# sensor.net
KiCad netlist of a schematic drawn in EAGLE
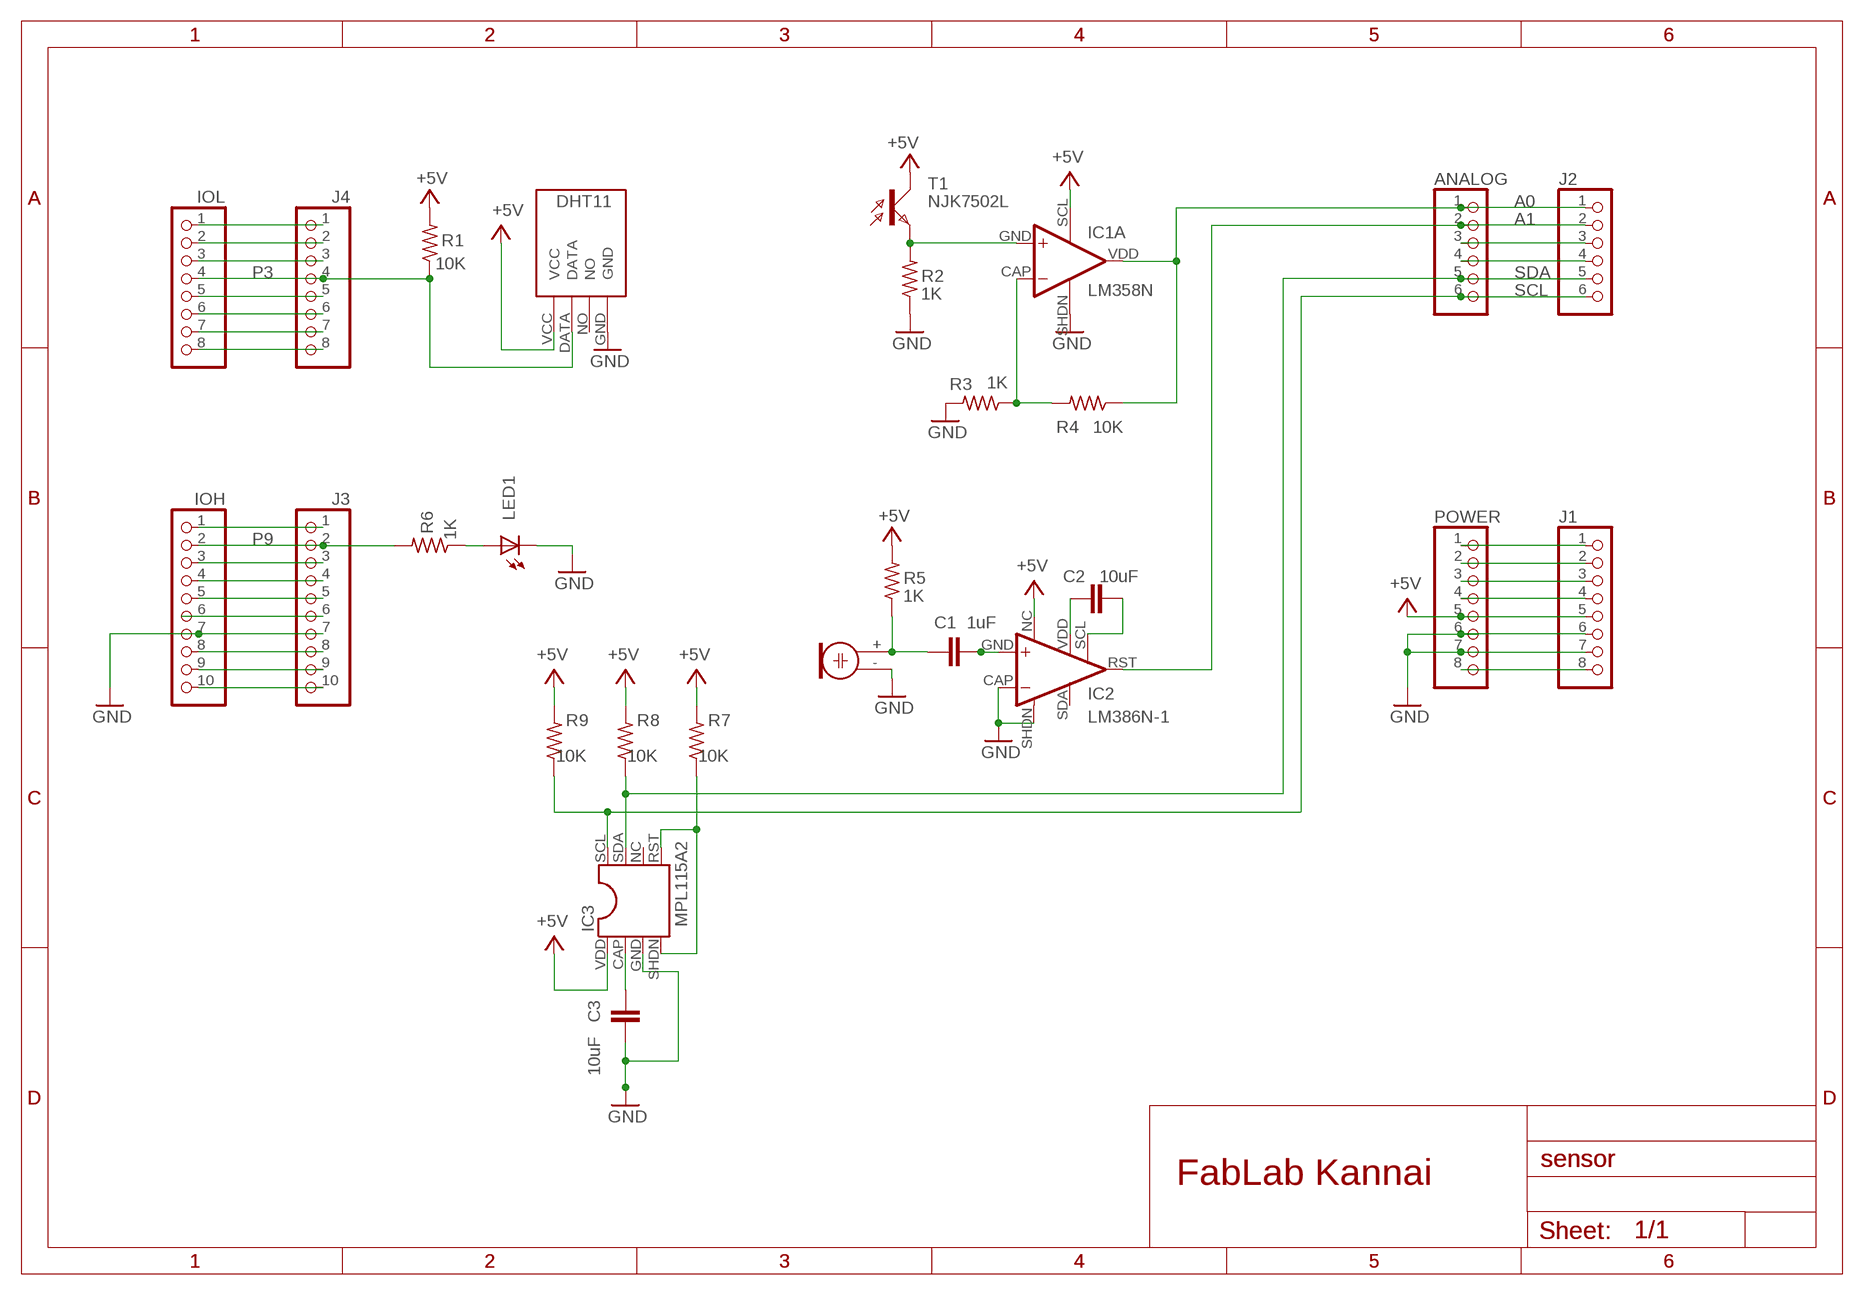
[diagram p0: schematic, sheet 1]

(export (version "E")
  (design (tool "Eeschema 10.0.6"))
  (components
    (comp (ref "ANALOG")
      (value "PINHD-1X6")
      (footprint "eagle-import:1X06")
      (libsource (lib "eagle-import") (part "PINHD-1X6"))
    )
    (comp (ref "C1")
      (value "1uF")
      (footprint "eagle-import:C025-025X050")
      (libsource (lib "eagle-import") (part "C-EU025-025X050"))
    )
    (comp (ref "C2")
      (value "10uF")
      (footprint "eagle-import:C025-025X050")
      (libsource (lib "eagle-import") (part "C-EU025-025X050"))
    )
    (comp (ref "C3")
      (value "10uF")
      (footprint "eagle-import:C025-025X050")
      (libsource (lib "eagle-import") (part "C-EU025-025X050"))
    )
    (comp (ref "IC1")
      (value "LM358N")
      (footprint "eagle-import:MPL115A2-DIL08")
      (libsource (lib "eagle-import") (part "LM358N"))
    )
    (comp (ref "IC2")
      (value "LM386N-1")
      (footprint "eagle-import:MPL115A2-DIL08")
      (libsource (lib "eagle-import") (part "LM386?-N1"))
    )
    (comp (ref "IC3")
      (value "MPL115A2")
      (footprint "eagle-import:MPL115A2-DIL08")
      (libsource (lib "eagle-import") (part "MPL115A2"))
    )
    (comp (ref "IOH")
      (value "PINHD-1X10TH")
      (footprint "eagle-import:1X10-TH")
      (libsource (lib "eagle-import") (part "PINHD-1X10TH"))
    )
    (comp (ref "IOL")
      (value "PINHD-1X8TH")
      (footprint "eagle-import:1X08-TH")
      (libsource (lib "eagle-import") (part "PINHD-1X8TH"))
    )
    (comp (ref "J1")
      (value "PINHD-1X8TH")
      (footprint "eagle-import:1X08-TH")
      (libsource (lib "eagle-import") (part "PINHD-1X8TH"))
    )
    (comp (ref "J2")
      (value "PINHD-1X6")
      (footprint "eagle-import:1X06")
      (libsource (lib "eagle-import") (part "PINHD-1X6"))
    )
    (comp (ref "J3")
      (value "PINHD-1X10TH")
      (footprint "eagle-import:1X10-TH")
      (libsource (lib "eagle-import") (part "PINHD-1X10TH"))
    )
    (comp (ref "J4")
      (value "PINHD-1X8TH")
      (footprint "eagle-import:1X08-TH")
      (libsource (lib "eagle-import") (part "PINHD-1X8TH"))
    )
    (comp (ref "LED1")
      (value "LED3MM")
      (footprint "eagle-import:LED3MM")
      (libsource (lib "eagle-import") (part "LED3MM"))
    )
    (comp (ref "M1")
      (value "C9257")
      (footprint "eagle-import:DB-C9767")
      (libsource (lib "eagle-import") (part "C9257{dblquote}{dblquote}"))
    )
    (comp (ref "POWER")
      (value "PINHD-1X8TH")
      (footprint "eagle-import:1X08-TH")
      (libsource (lib "eagle-import") (part "PINHD-1X8TH"))
    )
    (comp (ref "R1")
      (value "10K")
      (footprint "eagle-import:0204_7")
      (libsource (lib "eagle-import") (part "R-US_0204/7"))
    )
    (comp (ref "R2")
      (value "1K")
      (footprint "eagle-import:0204_7")
      (libsource (lib "eagle-import") (part "R-US_0204/7"))
    )
    (comp (ref "R3")
      (value "1K")
      (footprint "eagle-import:0204_7")
      (libsource (lib "eagle-import") (part "R-US_0204/7"))
    )
    (comp (ref "R4")
      (value "10K")
      (footprint "eagle-import:0204_7")
      (libsource (lib "eagle-import") (part "R-US_0204/7"))
    )
    (comp (ref "R5")
      (value "1K")
      (footprint "eagle-import:0204_7")
      (libsource (lib "eagle-import") (part "R-US_0204/7"))
    )
    (comp (ref "R6")
      (value "1K")
      (footprint "eagle-import:0204_7")
      (libsource (lib "eagle-import") (part "R-US_0204/7"))
    )
    (comp (ref "R7")
      (value "10K")
      (footprint "eagle-import:0204_7")
      (libsource (lib "eagle-import") (part "R-US_0204/7"))
    )
    (comp (ref "R8")
      (value "10K")
      (footprint "eagle-import:0204_7")
      (libsource (lib "eagle-import") (part "R-US_0204/7"))
    )
    (comp (ref "R9")
      (value "10K")
      (footprint "eagle-import:0204_7")
      (libsource (lib "eagle-import") (part "R-US_0204/7"))
    )
    (comp (ref "T1")
      (value "NJK7502L")
      (footprint "eagle-import:NJL7502L")
      (libsource (lib "eagle-import") (part "NJK7502L"))
    )
    (comp (ref "U$1")
      (value "DHT11")
      (footprint "eagle-import:DHT11")
      (libsource (lib "eagle-import") (part "DHT11"))
    )
  )
  (nets
    (net (code "1") (name "+5V") (class "Default")
      (node (ref "IC1") (pin "SCL") (pinfunction "V+_SCL") (pintype "power_in"))
      (node (ref "IC2") (pin "NC") (pinfunction "VS_NC") (pintype "power_in"))
      (node (ref "IC3") (pin "VDD") (pinfunction "VDD_VDD") (pintype "passive"))
      (node (ref "J1") (pin "5") (pinfunction "5_5") (pintype "passive"))
      (node (ref "POWER") (pin "5") (pinfunction "5_5") (pintype "passive"))
      (node (ref "R1") (pin "2") (pinfunction "2_2") (pintype "passive"))
      (node (ref "R5") (pin "2") (pinfunction "2_2") (pintype "passive"))
      (node (ref "R7") (pin "2") (pinfunction "2_2") (pintype "passive"))
      (node (ref "R8") (pin "2") (pinfunction "2_2") (pintype "passive"))
      (node (ref "R9") (pin "2") (pinfunction "2_2") (pintype "passive"))
      (node (ref "T1") (pin "C") (pinfunction "C_C") (pintype "passive"))
      (node (ref "U$1") (pin "VCC") (pinfunction "VCC_VCC") (pintype "bidirectional"))
    )
    (net (code "2") (name "/A0") (class "Default")
      (node (ref "ANALOG") (pin "1") (pinfunction "1_1") (pintype "passive"))
      (node (ref "IC1") (pin "VDD") (pinfunction "OUT_VDD") (pintype "output"))
      (node (ref "J2") (pin "1") (pinfunction "1_1") (pintype "passive"))
      (node (ref "R4") (pin "1") (pinfunction "1_1") (pintype "passive"))
    )
    (net (code "3") (name "/A1") (class "Default")
      (node (ref "ANALOG") (pin "2") (pinfunction "2_2") (pintype "passive"))
      (node (ref "IC2") (pin "RST") (pinfunction "OUT_RST") (pintype "output"))
      (node (ref "J2") (pin "2") (pinfunction "2_2") (pintype "passive"))
    )
    (net (code "4") (name "/P3") (class "Default")
      (node (ref "IOL") (pin "4") (pinfunction "4_4") (pintype "passive"))
      (node (ref "J4") (pin "4") (pinfunction "4_4") (pintype "passive"))
      (node (ref "R1") (pin "1") (pinfunction "1_1") (pintype "passive"))
      (node (ref "U$1") (pin "DATA") (pinfunction "DATA_DATA") (pintype "bidirectional"))
    )
    (net (code "5") (name "/P9") (class "Default")
      (node (ref "IOH") (pin "2") (pinfunction "2_2") (pintype "passive"))
      (node (ref "J3") (pin "2") (pinfunction "2_2") (pintype "passive"))
      (node (ref "R6") (pin "2") (pinfunction "2_2") (pintype "passive"))
    )
    (net (code "6") (name "/SCL") (class "Default")
      (node (ref "ANALOG") (pin "6") (pinfunction "6_6") (pintype "passive"))
      (node (ref "IC3") (pin "SCL") (pinfunction "SCL_SCL") (pintype "passive"))
      (node (ref "J2") (pin "6") (pinfunction "6_6") (pintype "passive"))
      (node (ref "R9") (pin "1") (pinfunction "1_1") (pintype "passive"))
    )
    (net (code "7") (name "/SDA") (class "Default")
      (node (ref "ANALOG") (pin "5") (pinfunction "5_5") (pintype "passive"))
      (node (ref "IC3") (pin "SDA") (pinfunction "SDA_SDA") (pintype "passive"))
      (node (ref "J2") (pin "5") (pinfunction "5_5") (pintype "passive"))
      (node (ref "R8") (pin "1") (pinfunction "1_1") (pintype "passive"))
    )
    (net (code "8") (name "GND") (class "Default")
      (node (ref "C3") (pin "2") (pinfunction "2_2") (pintype "passive"))
      (node (ref "IC1") (pin "SHDN") (pinfunction "V-_SHDN") (pintype "power_in"))
      (node (ref "IC2") (pin "CAP") (pinfunction "-IN_CAP") (pintype "input"))
      (node (ref "IC2") (pin "SHDN") (pinfunction "GND_SHDN") (pintype "power_in"))
      (node (ref "IC3") (pin "GND") (pinfunction "GND_GND") (pintype "passive"))
      (node (ref "IOH") (pin "7") (pinfunction "7_7") (pintype "passive"))
      (node (ref "J1") (pin "6") (pinfunction "6_6") (pintype "passive"))
      (node (ref "J1") (pin "7") (pinfunction "7_7") (pintype "passive"))
      (node (ref "J3") (pin "7") (pinfunction "7_7") (pintype "passive"))
      (node (ref "LED1") (pin "K") (pinfunction "C_K") (pintype "passive"))
      (node (ref "M1") (pin "-") (pinfunction "2_-") (pintype "passive"))
      (node (ref "POWER") (pin "6") (pinfunction "6_6") (pintype "passive"))
      (node (ref "POWER") (pin "7") (pinfunction "7_7") (pintype "passive"))
      (node (ref "R2") (pin "1") (pinfunction "1_1") (pintype "passive"))
      (node (ref "R3") (pin "2") (pinfunction "2_2") (pintype "passive"))
      (node (ref "U$1") (pin "GND") (pinfunction "GND_GND") (pintype "bidirectional"))
    )
    (net (code "9") (name "Net-(ANALOG-Pad3)") (class "Default")
      (node (ref "ANALOG") (pin "3") (pinfunction "3_3") (pintype "passive"))
      (node (ref "J2") (pin "3") (pinfunction "3_3") (pintype "passive"))
    )
    (net (code "10") (name "Net-(ANALOG-Pad4)") (class "Default")
      (node (ref "ANALOG") (pin "4") (pinfunction "4_4") (pintype "passive"))
      (node (ref "J2") (pin "4") (pinfunction "4_4") (pintype "passive"))
    )
    (net (code "11") (name "Net-(C2-Pad1)") (class "Default")
      (node (ref "C2") (pin "1") (pinfunction "1_1") (pintype "passive"))
      (node (ref "IC2") (pin "VDD") (pinfunction "GAIN_VDD") (pintype "passive"))
    )
    (net (code "12") (name "Net-(C2-Pad2)") (class "Default")
      (node (ref "C2") (pin "2") (pinfunction "2_2") (pintype "passive"))
      (node (ref "IC2") (pin "SCL") (pinfunction "GAIN_SCL") (pintype "passive"))
    )
    (net (code "13") (name "Net-(C3-Pad1)") (class "Default")
      (node (ref "C3") (pin "1") (pinfunction "1_1") (pintype "passive"))
      (node (ref "IC3") (pin "CAP") (pinfunction "CAP_CAP") (pintype "passive"))
    )
    (net (code "14") (name "Net-(IC1A-+IN)") (class "Default")
      (node (ref "IC1") (pin "GND") (pinfunction "+IN_GND") (pintype "input"))
      (node (ref "R2") (pin "2") (pinfunction "2_2") (pintype "passive"))
      (node (ref "T1") (pin "E") (pinfunction "E_E") (pintype "passive"))
    )
    (net (code "15") (name "Net-(IC1A--IN)") (class "Default")
      (node (ref "IC1") (pin "CAP") (pinfunction "-IN_CAP") (pintype "input"))
      (node (ref "R3") (pin "1") (pinfunction "1_1") (pintype "passive"))
      (node (ref "R4") (pin "2") (pinfunction "2_2") (pintype "passive"))
    )
    (net (code "16") (name "Net-(IC2-+IN)") (class "Default")
      (node (ref "C1") (pin "2") (pinfunction "2_2") (pintype "passive"))
      (node (ref "IC2") (pin "GND") (pinfunction "+IN_GND") (pintype "input"))
    )
    (net (code "17") (name "Net-(IC3-PadRST)") (class "Default")
      (node (ref "IC3") (pin "RST") (pinfunction "RST_RST") (pintype "passive"))
      (node (ref "IC3") (pin "SHDN") (pinfunction "SHDN_SHDN") (pintype "passive"))
      (node (ref "R7") (pin "1") (pinfunction "1_1") (pintype "passive"))
    )
    (net (code "18") (name "Net-(IOH-Pad1)") (class "Default")
      (node (ref "IOH") (pin "1") (pinfunction "1_1") (pintype "passive"))
      (node (ref "J3") (pin "1") (pinfunction "1_1") (pintype "passive"))
    )
    (net (code "19") (name "Net-(IOH-Pad3)") (class "Default")
      (node (ref "IOH") (pin "3") (pinfunction "3_3") (pintype "passive"))
      (node (ref "J3") (pin "3") (pinfunction "3_3") (pintype "passive"))
    )
    (net (code "20") (name "Net-(IOH-Pad4)") (class "Default")
      (node (ref "IOH") (pin "4") (pinfunction "4_4") (pintype "passive"))
      (node (ref "J3") (pin "4") (pinfunction "4_4") (pintype "passive"))
    )
    (net (code "21") (name "Net-(IOH-Pad5)") (class "Default")
      (node (ref "IOH") (pin "5") (pinfunction "5_5") (pintype "passive"))
      (node (ref "J3") (pin "5") (pinfunction "5_5") (pintype "passive"))
    )
    (net (code "22") (name "Net-(IOH-Pad6)") (class "Default")
      (node (ref "IOH") (pin "6") (pinfunction "6_6") (pintype "passive"))
      (node (ref "J3") (pin "6") (pinfunction "6_6") (pintype "passive"))
    )
    (net (code "23") (name "Net-(IOH-Pad8)") (class "Default")
      (node (ref "IOH") (pin "8") (pinfunction "8_8") (pintype "passive"))
      (node (ref "J3") (pin "8") (pinfunction "8_8") (pintype "passive"))
    )
    (net (code "24") (name "Net-(IOH-Pad9)") (class "Default")
      (node (ref "IOH") (pin "9") (pinfunction "9_9") (pintype "passive"))
      (node (ref "J3") (pin "9") (pinfunction "9_9") (pintype "passive"))
    )
    (net (code "25") (name "Net-(IOH-Pad10)") (class "Default")
      (node (ref "IOH") (pin "10") (pinfunction "10_10") (pintype "passive"))
      (node (ref "J3") (pin "10") (pinfunction "10_10") (pintype "passive"))
    )
    (net (code "26") (name "Net-(IOL-Pad1)") (class "Default")
      (node (ref "IOL") (pin "1") (pinfunction "1_1") (pintype "passive"))
      (node (ref "J4") (pin "1") (pinfunction "1_1") (pintype "passive"))
    )
    (net (code "27") (name "Net-(IOL-Pad2)") (class "Default")
      (node (ref "IOL") (pin "2") (pinfunction "2_2") (pintype "passive"))
      (node (ref "J4") (pin "2") (pinfunction "2_2") (pintype "passive"))
    )
    (net (code "28") (name "Net-(IOL-Pad3)") (class "Default")
      (node (ref "IOL") (pin "3") (pinfunction "3_3") (pintype "passive"))
      (node (ref "J4") (pin "3") (pinfunction "3_3") (pintype "passive"))
    )
    (net (code "29") (name "Net-(IOL-Pad5)") (class "Default")
      (node (ref "IOL") (pin "5") (pinfunction "5_5") (pintype "passive"))
      (node (ref "J4") (pin "5") (pinfunction "5_5") (pintype "passive"))
    )
    (net (code "30") (name "Net-(IOL-Pad6)") (class "Default")
      (node (ref "IOL") (pin "6") (pinfunction "6_6") (pintype "passive"))
      (node (ref "J4") (pin "6") (pinfunction "6_6") (pintype "passive"))
    )
    (net (code "31") (name "Net-(IOL-Pad7)") (class "Default")
      (node (ref "IOL") (pin "7") (pinfunction "7_7") (pintype "passive"))
      (node (ref "J4") (pin "7") (pinfunction "7_7") (pintype "passive"))
    )
    (net (code "32") (name "Net-(IOL-Pad8)") (class "Default")
      (node (ref "IOL") (pin "8") (pinfunction "8_8") (pintype "passive"))
      (node (ref "J4") (pin "8") (pinfunction "8_8") (pintype "passive"))
    )
    (net (code "33") (name "Net-(J1-Pad1)") (class "Default")
      (node (ref "J1") (pin "1") (pinfunction "1_1") (pintype "passive"))
      (node (ref "POWER") (pin "1") (pinfunction "1_1") (pintype "passive"))
    )
    (net (code "34") (name "Net-(J1-Pad2)") (class "Default")
      (node (ref "J1") (pin "2") (pinfunction "2_2") (pintype "passive"))
      (node (ref "POWER") (pin "2") (pinfunction "2_2") (pintype "passive"))
    )
    (net (code "35") (name "Net-(J1-Pad3)") (class "Default")
      (node (ref "J1") (pin "3") (pinfunction "3_3") (pintype "passive"))
      (node (ref "POWER") (pin "3") (pinfunction "3_3") (pintype "passive"))
    )
    (net (code "36") (name "Net-(J1-Pad4)") (class "Default")
      (node (ref "J1") (pin "4") (pinfunction "4_4") (pintype "passive"))
      (node (ref "POWER") (pin "4") (pinfunction "4_4") (pintype "passive"))
    )
    (net (code "37") (name "Net-(J1-Pad8)") (class "Default")
      (node (ref "J1") (pin "8") (pinfunction "8_8") (pintype "passive"))
      (node (ref "POWER") (pin "8") (pinfunction "8_8") (pintype "passive"))
    )
    (net (code "38") (name "Net-(LED1-PadA)") (class "Default")
      (node (ref "LED1") (pin "A") (pinfunction "A_A") (pintype "passive"))
      (node (ref "R6") (pin "1") (pinfunction "1_1") (pintype "passive"))
    )
    (net (code "39") (name "Net-(M1-1)") (class "Default")
      (node (ref "C1") (pin "1") (pinfunction "1_1") (pintype "passive"))
      (node (ref "M1") (pin "+") (pinfunction "1_+") (pintype "passive"))
      (node (ref "R5") (pin "1") (pinfunction "1_1") (pintype "passive"))
    )
    (net (code "40") (name "unconnected-(IC2-BYPASS-PadSDA)") (class "Default")
      (node (ref "IC2") (pin "SDA") (pinfunction "BYPASS_SDA") (pintype "passive"))
    )
    (net (code "41") (name "unconnected-(IC3-PadNC)") (class "Default")
      (node (ref "IC3") (pin "NC") (pinfunction "NC_NC") (pintype "passive"))
    )
    (net (code "42") (name "unconnected-(U$1-PadNO)") (class "Default")
      (node (ref "U$1") (pin "NO") (pinfunction "NO_NO") (pintype "bidirectional"))
    )
  )
)
